# NuMulti_Adaptor_Board.net
KiCad netlist of a schematic drawn in EAGLE
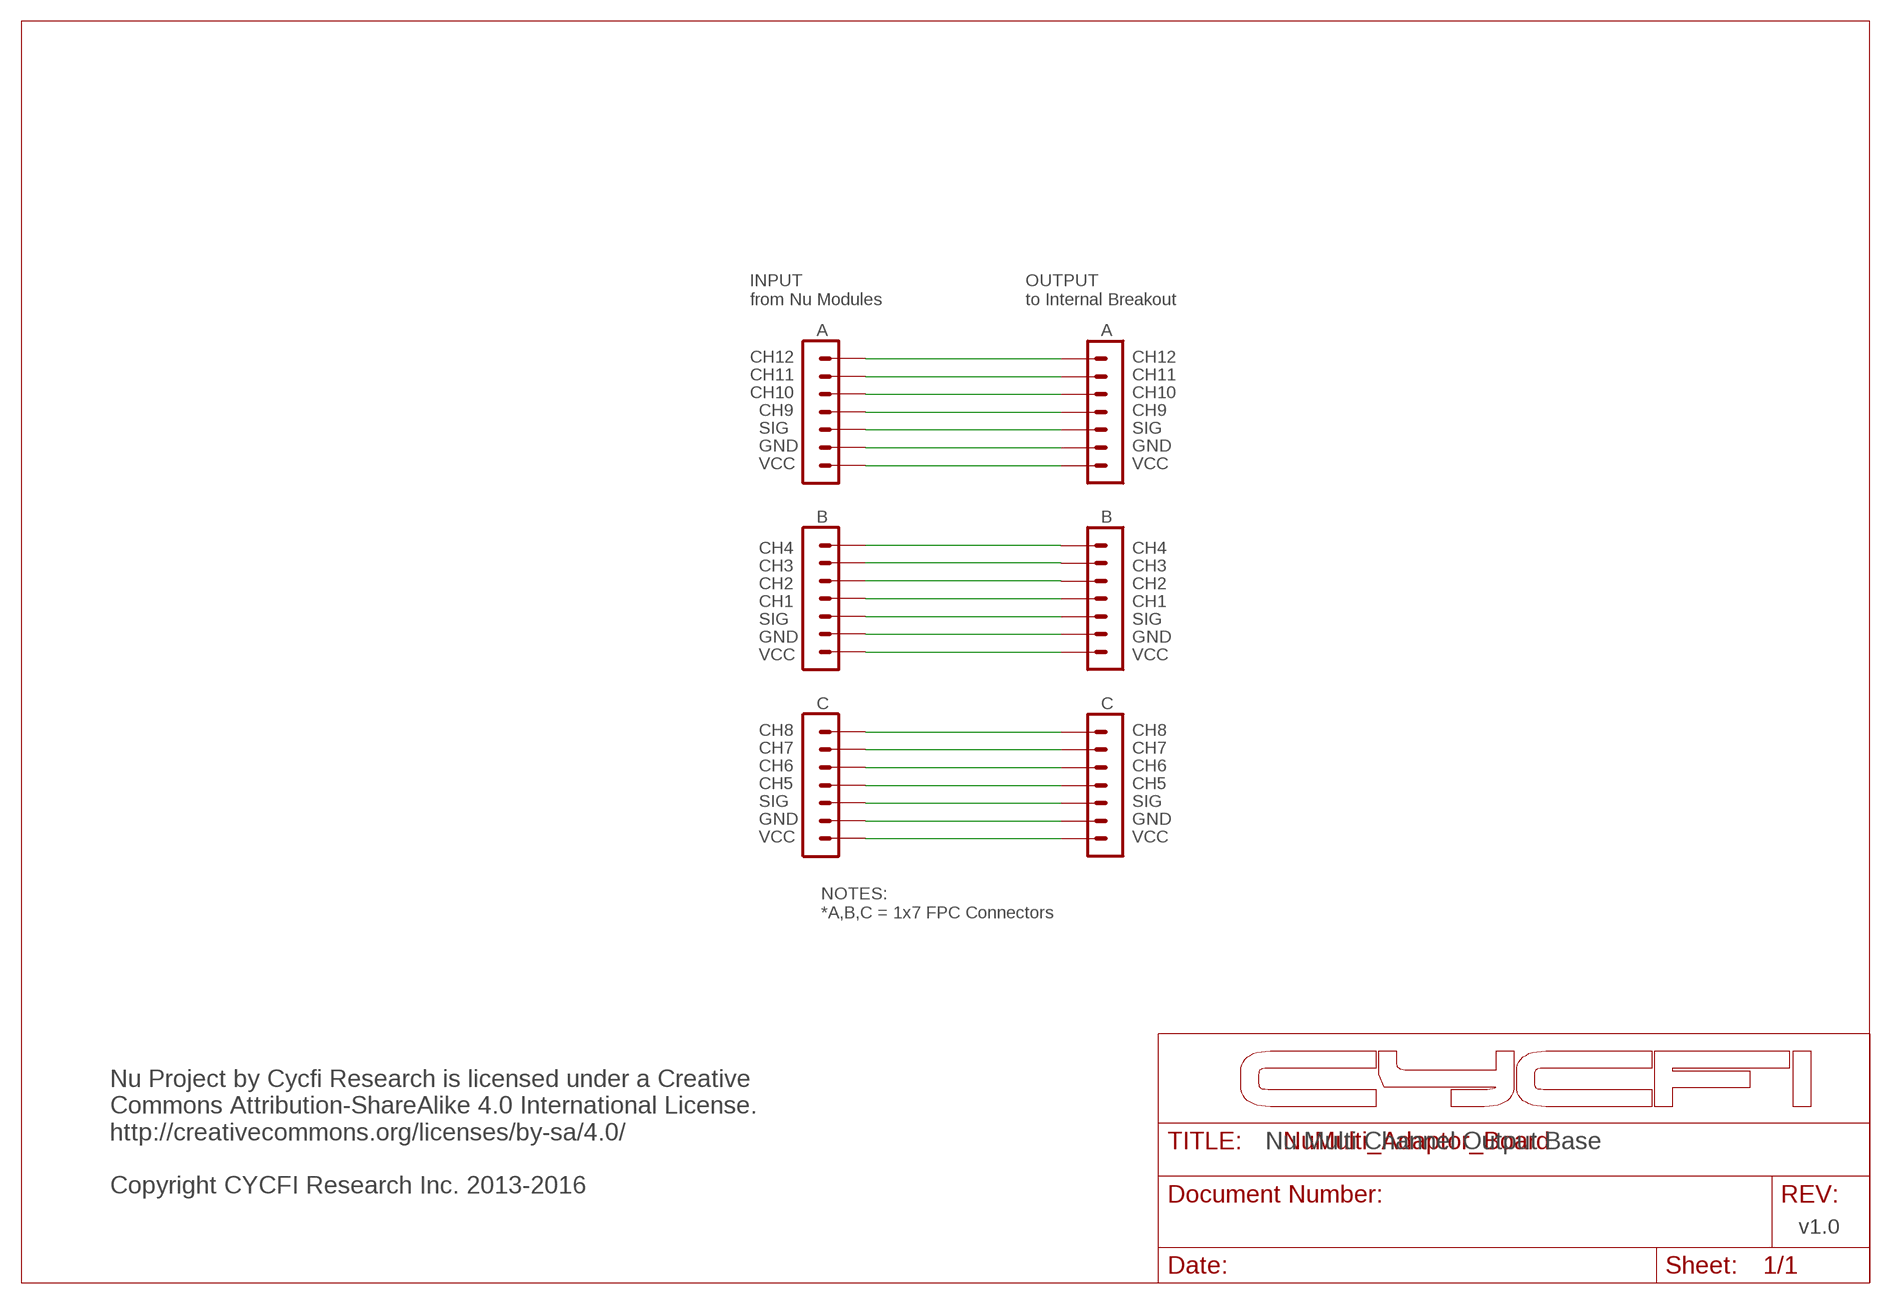
[diagram p0: schematic, sheet 1]

(export (version "E")
  (design (tool "Eeschema 10.0.6"))
  (components
    (comp (ref "H1")
      (value "7P_ZIF_59453-071110EDHLF")
      (footprint "eagle-import:7P_ZIF_59453-071110EDHLF")
      (libsource (lib "eagle-import") (part "7P_ZIF_59453-071110EDHLF"))
    )
    (comp (ref "H2")
      (value "7P_ZIF_59453-071110EDHLF")
      (footprint "eagle-import:7P_ZIF_59453-071110EDHLF")
      (libsource (lib "eagle-import") (part "7P_ZIF_59453-071110EDHLF"))
    )
    (comp (ref "H3")
      (value "7P_ZIF_59453-071110EDHLF")
      (footprint "eagle-import:7P_ZIF_59453-071110EDHLF")
      (libsource (lib "eagle-import") (part "7P_ZIF_59453-071110EDHLF"))
    )
    (comp (ref "H4")
      (value "7P_ZIF_59453-071110EDHLF")
      (footprint "eagle-import:7P_ZIF_59453-071110EDHLF")
      (libsource (lib "eagle-import") (part "7P_ZIF_59453-071110EDHLF"))
    )
    (comp (ref "H5")
      (value "7P_ZIF_59453-071110EDHLF")
      (footprint "eagle-import:7P_ZIF_59453-071110EDHLF")
      (libsource (lib "eagle-import") (part "7P_ZIF_59453-071110EDHLF"))
    )
    (comp (ref "H6")
      (value "7P_ZIF_59453-071110EDHLF")
      (footprint "eagle-import:7P_ZIF_59453-071110EDHLF")
      (libsource (lib "eagle-import") (part "7P_ZIF_59453-071110EDHLF"))
    )
  )
  (nets
    (net (code "1") (name "/GND") (class "Default")
      (node (ref "H1") (pin "P$6") (pinfunction "6_P$6") (pintype "passive"))
      (node (ref "H2") (pin "P$6") (pinfunction "6_P$6") (pintype "passive"))
      (node (ref "H3") (pin "P$6") (pinfunction "6_P$6") (pintype "passive"))
      (node (ref "H4") (pin "P$6") (pinfunction "6_P$6") (pintype "passive"))
      (node (ref "H5") (pin "P$6") (pinfunction "6_P$6") (pintype "passive"))
      (node (ref "H6") (pin "P$6") (pinfunction "6_P$6") (pintype "passive"))
    )
    (net (code "2") (name "Net-(H1-1)") (class "Default")
      (node (ref "H1") (pin "P$1") (pinfunction "1_P$1") (pintype "passive"))
      (node (ref "H3") (pin "P$1") (pinfunction "1_P$1") (pintype "passive"))
    )
    (net (code "3") (name "Net-(H1-2)") (class "Default")
      (node (ref "H1") (pin "P$2") (pinfunction "2_P$2") (pintype "passive"))
      (node (ref "H3") (pin "P$2") (pinfunction "2_P$2") (pintype "passive"))
    )
    (net (code "4") (name "Net-(H1-3)") (class "Default")
      (node (ref "H1") (pin "P$3") (pinfunction "3_P$3") (pintype "passive"))
      (node (ref "H3") (pin "P$3") (pinfunction "3_P$3") (pintype "passive"))
    )
    (net (code "5") (name "Net-(H1-4)") (class "Default")
      (node (ref "H1") (pin "P$4") (pinfunction "4_P$4") (pintype "passive"))
      (node (ref "H3") (pin "P$4") (pinfunction "4_P$4") (pintype "passive"))
    )
    (net (code "6") (name "Net-(H1-5)") (class "Default")
      (node (ref "H1") (pin "P$5") (pinfunction "5_P$5") (pintype "passive"))
      (node (ref "H3") (pin "P$5") (pinfunction "5_P$5") (pintype "passive"))
    )
    (net (code "7") (name "Net-(H1-7)") (class "Default")
      (node (ref "H1") (pin "P$7") (pinfunction "7_P$7") (pintype "passive"))
      (node (ref "H3") (pin "P$7") (pinfunction "7_P$7") (pintype "passive"))
    )
    (net (code "8") (name "Net-(H2-1)") (class "Default")
      (node (ref "H2") (pin "P$1") (pinfunction "1_P$1") (pintype "passive"))
      (node (ref "H4") (pin "P$1") (pinfunction "1_P$1") (pintype "passive"))
    )
    (net (code "9") (name "Net-(H2-2)") (class "Default")
      (node (ref "H2") (pin "P$2") (pinfunction "2_P$2") (pintype "passive"))
      (node (ref "H4") (pin "P$2") (pinfunction "2_P$2") (pintype "passive"))
    )
    (net (code "10") (name "Net-(H2-3)") (class "Default")
      (node (ref "H2") (pin "P$3") (pinfunction "3_P$3") (pintype "passive"))
      (node (ref "H4") (pin "P$3") (pinfunction "3_P$3") (pintype "passive"))
    )
    (net (code "11") (name "Net-(H2-4)") (class "Default")
      (node (ref "H2") (pin "P$4") (pinfunction "4_P$4") (pintype "passive"))
      (node (ref "H4") (pin "P$4") (pinfunction "4_P$4") (pintype "passive"))
    )
    (net (code "12") (name "Net-(H2-5)") (class "Default")
      (node (ref "H2") (pin "P$5") (pinfunction "5_P$5") (pintype "passive"))
      (node (ref "H4") (pin "P$5") (pinfunction "5_P$5") (pintype "passive"))
    )
    (net (code "13") (name "Net-(H2-7)") (class "Default")
      (node (ref "H2") (pin "P$7") (pinfunction "7_P$7") (pintype "passive"))
      (node (ref "H4") (pin "P$7") (pinfunction "7_P$7") (pintype "passive"))
    )
    (net (code "14") (name "Net-(H5-1)") (class "Default")
      (node (ref "H5") (pin "P$1") (pinfunction "1_P$1") (pintype "passive"))
      (node (ref "H6") (pin "P$1") (pinfunction "1_P$1") (pintype "passive"))
    )
    (net (code "15") (name "Net-(H5-2)") (class "Default")
      (node (ref "H5") (pin "P$2") (pinfunction "2_P$2") (pintype "passive"))
      (node (ref "H6") (pin "P$2") (pinfunction "2_P$2") (pintype "passive"))
    )
    (net (code "16") (name "Net-(H5-3)") (class "Default")
      (node (ref "H5") (pin "P$3") (pinfunction "3_P$3") (pintype "passive"))
      (node (ref "H6") (pin "P$3") (pinfunction "3_P$3") (pintype "passive"))
    )
    (net (code "17") (name "Net-(H5-4)") (class "Default")
      (node (ref "H5") (pin "P$4") (pinfunction "4_P$4") (pintype "passive"))
      (node (ref "H6") (pin "P$4") (pinfunction "4_P$4") (pintype "passive"))
    )
    (net (code "18") (name "Net-(H5-5)") (class "Default")
      (node (ref "H5") (pin "P$5") (pinfunction "5_P$5") (pintype "passive"))
      (node (ref "H6") (pin "P$5") (pinfunction "5_P$5") (pintype "passive"))
    )
    (net (code "19") (name "Net-(H5-7)") (class "Default")
      (node (ref "H5") (pin "P$7") (pinfunction "7_P$7") (pintype "passive"))
      (node (ref "H6") (pin "P$7") (pinfunction "7_P$7") (pintype "passive"))
    )
  )
)
